# AD8302.net
KiCad netlist of a schematic drawn in EasyEDA Pro
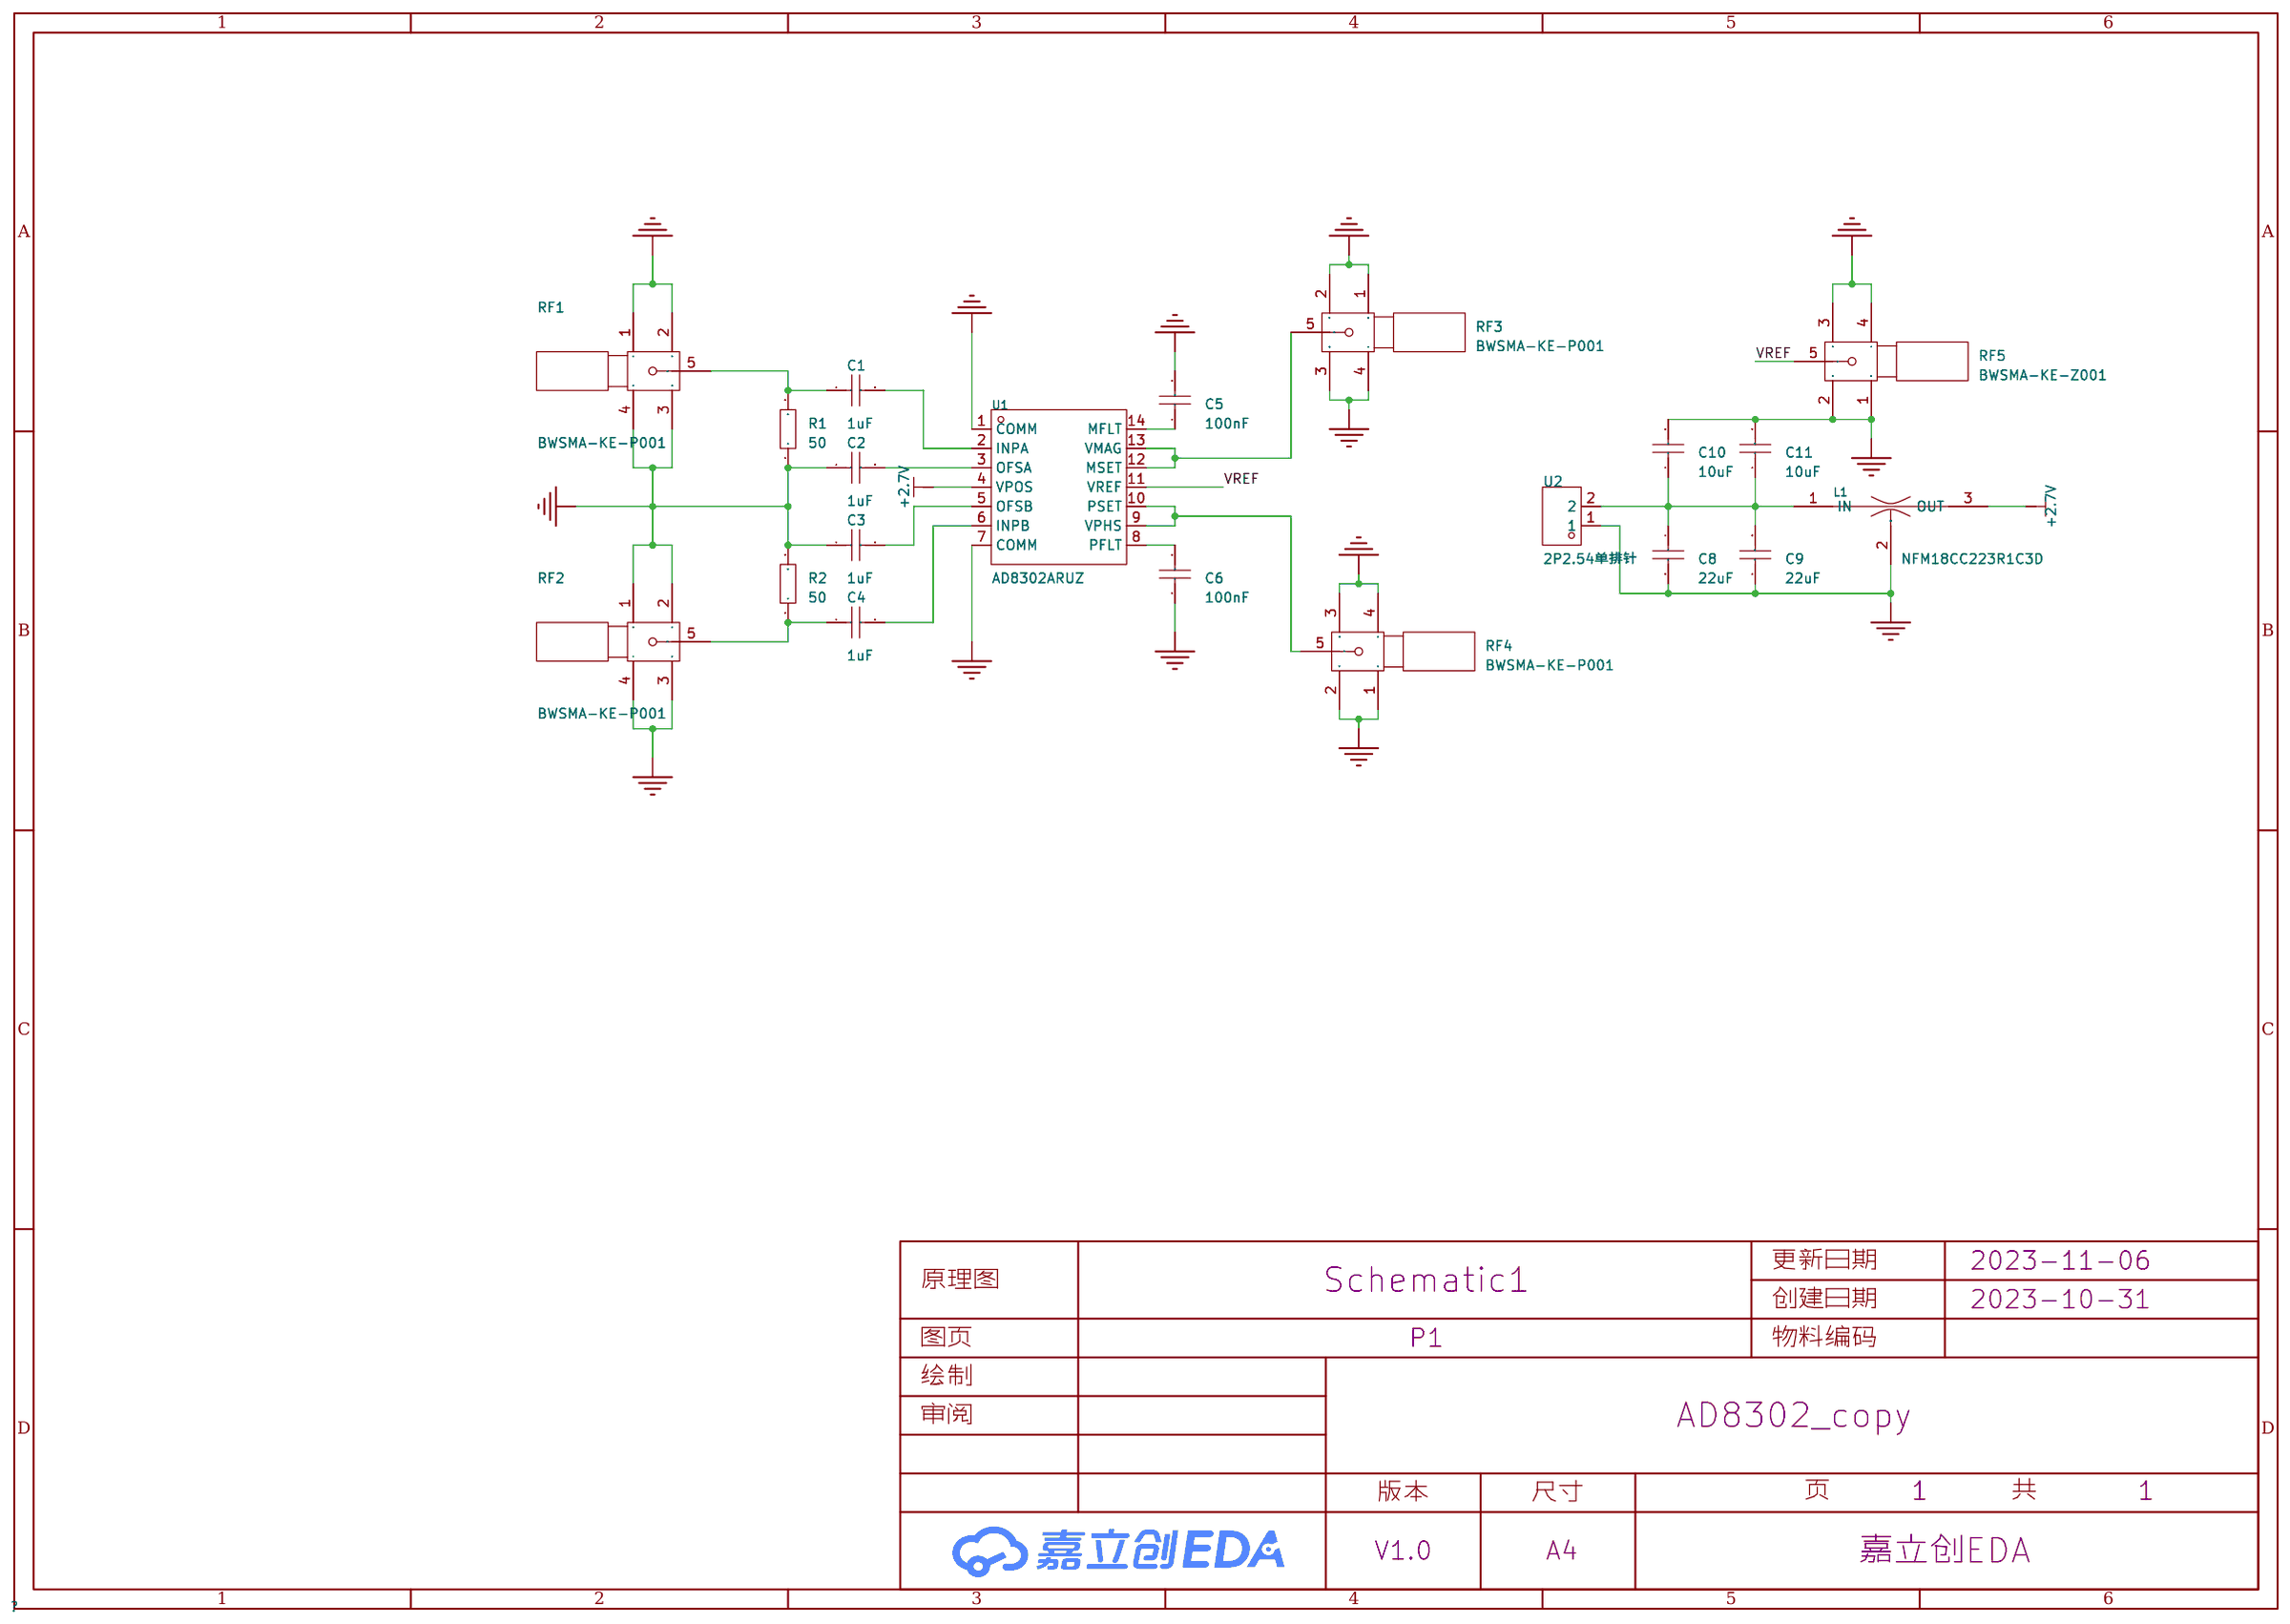
[diagram p0: schematic sheet]

(export (version "E")
  (design (tool "Eeschema 10.0.6"))
  (components
    (comp (ref "C1")
      (value "1uF")
      (footprint "easyedapro:C0603")
      (description "容值:1uF;精度:±10%;额定电压:50V;材质(温度系数):X5R;")
      (fields
        (field (name "Manufacturer Part") "CL10A105KB8NNNC")
        (field (name "Manufacturer") "SAMSUNG(三星)")
      )
      (libsource (lib "easyedapro") (part "CL10A105KB8NNNC"))
    )
    (comp (ref "C2")
      (value "1uF")
      (footprint "easyedapro:C0603")
      (description "容值:1uF;精度:±10%;额定电压:50V;材质(温度系数):X5R;")
      (fields
        (field (name "Manufacturer Part") "CL10A105KB8NNNC")
        (field (name "Manufacturer") "SAMSUNG(三星)")
      )
      (libsource (lib "easyedapro") (part "CL10A105KB8NNNC"))
    )
    (comp (ref "C3")
      (value "1uF")
      (footprint "easyedapro:C0603")
      (description "容值:1uF;精度:±10%;额定电压:50V;材质(温度系数):X5R;")
      (fields
        (field (name "Manufacturer Part") "CL10A105KB8NNNC")
        (field (name "Manufacturer") "SAMSUNG(三星)")
      )
      (libsource (lib "easyedapro") (part "CL10A105KB8NNNC"))
    )
    (comp (ref "C4")
      (value "1uF")
      (footprint "easyedapro:C0603")
      (description "容值:1uF;精度:±10%;额定电压:50V;材质(温度系数):X5R;")
      (fields
        (field (name "Manufacturer Part") "CL10A105KB8NNNC")
        (field (name "Manufacturer") "SAMSUNG(三星)")
      )
      (libsource (lib "easyedapro") (part "CL10A105KB8NNNC"))
    )
    (comp (ref "C5")
      (value "100nF")
      (footprint "easyedapro:C0603")
      (description "容值:1uF;精度:±10%;额定电压:50V;材质(温度系数):X5R;")
      (fields
        (field (name "Manufacturer Part") "CL10A105KB8NNNC")
        (field (name "Manufacturer") "SAMSUNG(三星)")
      )
      (libsource (lib "easyedapro") (part "CL10A105KB8NNNC"))
    )
    (comp (ref "C6")
      (value "100nF")
      (footprint "easyedapro:C0603")
      (description "容值:1uF;精度:±10%;额定电压:50V;材质(温度系数):X5R;")
      (fields
        (field (name "Manufacturer Part") "CL10A105KB8NNNC")
        (field (name "Manufacturer") "SAMSUNG(三星)")
      )
      (libsource (lib "easyedapro") (part "CL10A105KB8NNNC"))
    )
    (comp (ref "C8")
      (value "22uF")
      (footprint "easyedapro:C0603")
      (description "容值:1uF;精度:±10%;额定电压:50V;材质(温度系数):X5R;")
      (fields
        (field (name "Manufacturer Part") "CL10A105KB8NNNC")
        (field (name "Manufacturer") "SAMSUNG(三星)")
      )
      (libsource (lib "easyedapro") (part "CL10A105KB8NNNC"))
    )
    (comp (ref "C9")
      (value "22uF")
      (footprint "easyedapro:C0603")
      (description "容值:1uF;精度:±10%;额定电压:50V;材质(温度系数):X5R;")
      (fields
        (field (name "Manufacturer Part") "CL10A105KB8NNNC")
        (field (name "Manufacturer") "SAMSUNG(三星)")
      )
      (libsource (lib "easyedapro") (part "CL10A105KB8NNNC"))
    )
    (comp (ref "C10")
      (value "10uF")
      (footprint "easyedapro:C0603")
      (description "容值:1uF;精度:±10%;额定电压:50V;材质(温度系数):X5R;")
      (fields
        (field (name "Manufacturer Part") "CL10A105KB8NNNC")
        (field (name "Manufacturer") "SAMSUNG(三星)")
      )
      (libsource (lib "easyedapro") (part "CL10A105KB8NNNC"))
    )
    (comp (ref "C11")
      (value "10uF")
      (footprint "easyedapro:C0603")
      (description "容值:1uF;精度:±10%;额定电压:50V;材质(温度系数):X5R;")
      (fields
        (field (name "Manufacturer Part") "CL10A105KB8NNNC")
        (field (name "Manufacturer") "SAMSUNG(三星)")
      )
      (libsource (lib "easyedapro") (part "CL10A105KB8NNNC"))
    )
    (comp (ref "L1")
      (value "NFM18CC223R1C3D")
      (footprint "easyedapro:FILTER-SMD_3P-L1.6-W0.8-L_NFM18CC223R1C3D")
      (description "电容量:22nF;精度:±20%;直流电阻:50mΩ;")
      (fields (field (name "Manufacturer") "muRata(村田)"))
      (libsource (lib "easyedapro") (part "NFM18CC223R1C3D"))
    )
    (comp (ref "R1") (value "50") (footprint "easyedapro:R0603") (libsource (lib "easyedapro") (part "电阻")))
    (comp (ref "R2") (value "50") (footprint "easyedapro:R0603") (libsource (lib "easyedapro") (part "电阻")))
    (comp (ref "RF1")
      (value "BWSMA-KE-P001")
      (footprint "easyedapro:SMA-SMD_BWSMA-KE-P001")
      (description "连接器类型:板端;射频系列:SMA;接口类型:内孔;端口数量:1;阻抗:50Ω;频率-最大值:12.4GHz;样式:偏脚;接口直径:5.2mm;接口长度/高度:-;工作温度范围:-;")
      (fields (field (name "Manufacturer") "BAT WIRELESS(蝙蝠无线)"))
      (libsource (lib "easyedapro") (part "BWSMA-KE-P001"))
    )
    (comp (ref "RF2")
      (value "BWSMA-KE-P001")
      (footprint "easyedapro:SMA-SMD_BWSMA-KE-P001")
      (description "连接器类型:板端;射频系列:SMA;接口类型:内孔;端口数量:1;阻抗:50Ω;频率-最大值:12.4GHz;样式:偏脚;接口直径:5.2mm;接口长度/高度:-;工作温度范围:-;")
      (fields (field (name "Manufacturer") "BAT WIRELESS(蝙蝠无线)"))
      (libsource (lib "easyedapro") (part "BWSMA-KE-P001"))
    )
    (comp (ref "RF3")
      (value "BWSMA-KE-P001")
      (footprint "easyedapro:SMA-SMD_BWSMA-KE-P001")
      (description "连接器类型:板端;射频系列:SMA;接口类型:内孔;端口数量:1;阻抗:50Ω;频率-最大值:12.4GHz;样式:偏脚;接口直径:5.2mm;接口长度/高度:-;工作温度范围:-;")
      (fields (field (name "Manufacturer") "BAT WIRELESS(蝙蝠无线)"))
      (libsource (lib "easyedapro") (part "BWSMA-KE-P001"))
    )
    (comp (ref "RF4")
      (value "BWSMA-KE-P001")
      (footprint "easyedapro:SMA-SMD_BWSMA-KE-P001")
      (description "连接器类型:板端;射频系列:SMA;接口类型:内孔;端口数量:1;阻抗:50Ω;频率-最大值:12.4GHz;样式:偏脚;接口直径:5.2mm;接口长度/高度:-;工作温度范围:-;")
      (fields (field (name "Manufacturer") "BAT WIRELESS(蝙蝠无线)"))
      (libsource (lib "easyedapro") (part "BWSMA-KE-P001"))
    )
    (comp (ref "RF5")
      (value "BWSMA-KE-Z001")
      (footprint "easyedapro:SMA-TH_BWSMA-KE-Z001")
      (description "连接器类型:板端;射频系列:SMA;接口类型:内孔;端口数量:1;阻抗:50Ω;频率-最大值:12.4GHz;样式:正脚;接口直径:-;接口长度/高度:-;工作温度范围:-65°C~+165°C;")
      (fields (field (name "Manufacturer") "BAT WIRELESS(蝙蝠无线)"))
      (libsource (lib "easyedapro") (part "BWSMA-KE-Z001"))
    )
    (comp (ref "U1")
      (value "AD8302ARUZ")
      (footprint "easyedapro:TSSOP-14_L5.0-W4.4-P0.65-LS6.4-BL")
      (description "应用领域:通用;频率范围:2.7GHz;输入范围:-60dBm~0dBm;精度:±0.5dB;")
      (fields (field (name "Manufacturer") "ADI(亚德诺)"))
      (libsource (lib "easyedapro") (part "AD8302ARUZ"))
    )
    (comp (ref "U2")
      (value "2P2.54单排针")
      (footprint "easyedapro:HDR-TH_2P-P2.54-V-M")
      (libsource (lib "easyedapro") (part "2P2.54单排针"))
    )
  )
  (nets
    (net (code "1") (name "+2.7V") (class "Default")
      (node (ref "L1") (pin "3") (pinfunction "OUT_3") (pintype "input"))
      (node (ref "U1") (pin "4") (pinfunction "VPOS_4") (pintype "input"))
    )
    (net (code "2") (name "/VREF") (class "Default")
      (node (ref "RF5") (pin "5") (pinfunction "5_5") (pintype "input"))
      (node (ref "U1") (pin "11") (pinfunction "VREF_11") (pintype "input"))
    )
    (net (code "3") (name "GND") (class "Default")
      (node (ref "C10") (pin "2") (pinfunction "2_2") (pintype "input"))
      (node (ref "C11") (pin "2") (pinfunction "2_2") (pintype "input"))
      (node (ref "C2") (pin "1") (pinfunction "1_1") (pintype "input"))
      (node (ref "C3") (pin "1") (pinfunction "1_1") (pintype "input"))
      (node (ref "C5") (pin "2") (pinfunction "2_2") (pintype "input"))
      (node (ref "C6") (pin "2") (pinfunction "2_2") (pintype "input"))
      (node (ref "C8") (pin "2") (pinfunction "2_2") (pintype "input"))
      (node (ref "C9") (pin "1") (pinfunction "1_1") (pintype "input"))
      (node (ref "L1") (pin "2") (pinfunction "GND_2") (pintype "input"))
      (node (ref "R1") (pin "1") (pinfunction "1_1") (pintype "input"))
      (node (ref "R2") (pin "2") (pinfunction "2_2") (pintype "input"))
      (node (ref "RF1") (pin "1") (pinfunction "1_1") (pintype "input"))
      (node (ref "RF1") (pin "2") (pinfunction "2_2") (pintype "input"))
      (node (ref "RF1") (pin "3") (pinfunction "3_3") (pintype "input"))
      (node (ref "RF1") (pin "4") (pinfunction "4_4") (pintype "input"))
      (node (ref "RF2") (pin "1") (pinfunction "1_1") (pintype "input"))
      (node (ref "RF2") (pin "2") (pinfunction "2_2") (pintype "input"))
      (node (ref "RF2") (pin "3") (pinfunction "3_3") (pintype "input"))
      (node (ref "RF2") (pin "4") (pinfunction "4_4") (pintype "input"))
      (node (ref "RF3") (pin "1") (pinfunction "1_1") (pintype "input"))
      (node (ref "RF3") (pin "2") (pinfunction "2_2") (pintype "input"))
      (node (ref "RF3") (pin "3") (pinfunction "3_3") (pintype "input"))
      (node (ref "RF3") (pin "4") (pinfunction "4_4") (pintype "input"))
      (node (ref "RF4") (pin "1") (pinfunction "1_1") (pintype "input"))
      (node (ref "RF4") (pin "2") (pinfunction "2_2") (pintype "input"))
      (node (ref "RF4") (pin "3") (pinfunction "3_3") (pintype "input"))
      (node (ref "RF4") (pin "4") (pinfunction "4_4") (pintype "input"))
      (node (ref "RF5") (pin "1") (pinfunction "1_1") (pintype "input"))
      (node (ref "RF5") (pin "2") (pinfunction "2_2") (pintype "input"))
      (node (ref "RF5") (pin "3") (pinfunction "3_3") (pintype "input"))
      (node (ref "RF5") (pin "4") (pinfunction "4_4") (pintype "input"))
      (node (ref "U1") (pin "1") (pinfunction "COMM_1") (pintype "input"))
      (node (ref "U1") (pin "7") (pinfunction "COMM_7") (pintype "input"))
      (node (ref "U2") (pin "1") (pinfunction "1_1") (pintype "input"))
    )
    (net (code "4") (name "Net-(C1-Pad1)") (class "Default")
      (node (ref "C1") (pin "1") (pinfunction "1_1") (pintype "input"))
      (node (ref "R1") (pin "2") (pinfunction "2_2") (pintype "input"))
      (node (ref "RF1") (pin "5") (pinfunction "5_5") (pintype "input"))
    )
    (net (code "5") (name "Net-(C4-Pad1)") (class "Default")
      (node (ref "C4") (pin "1") (pinfunction "1_1") (pintype "input"))
      (node (ref "R2") (pin "1") (pinfunction "1_1") (pintype "input"))
      (node (ref "RF2") (pin "5") (pinfunction "5_5") (pintype "input"))
    )
    (net (code "6") (name "Net-(L1-IN)") (class "Default")
      (node (ref "C10") (pin "1") (pinfunction "1_1") (pintype "input"))
      (node (ref "C11") (pin "1") (pinfunction "1_1") (pintype "input"))
      (node (ref "C8") (pin "1") (pinfunction "1_1") (pintype "input"))
      (node (ref "C9") (pin "2") (pinfunction "2_2") (pintype "input"))
      (node (ref "L1") (pin "1") (pinfunction "IN_1") (pintype "input"))
      (node (ref "U2") (pin "2") (pinfunction "2_2") (pintype "input"))
    )
    (net (code "7") (name "Net-(U1-INPA)") (class "Default")
      (node (ref "C1") (pin "2") (pinfunction "2_2") (pintype "input"))
      (node (ref "U1") (pin "2") (pinfunction "INPA_2") (pintype "input"))
    )
    (net (code "8") (name "Net-(U1-INPB)") (class "Default")
      (node (ref "C4") (pin "2") (pinfunction "2_2") (pintype "input"))
      (node (ref "U1") (pin "6") (pinfunction "INPB_6") (pintype "input"))
    )
    (net (code "9") (name "Net-(U1-MFLT)") (class "Default")
      (node (ref "C5") (pin "1") (pinfunction "1_1") (pintype "input"))
      (node (ref "U1") (pin "14") (pinfunction "MFLT_14") (pintype "input"))
    )
    (net (code "10") (name "Net-(U1-MSET)") (class "Default")
      (node (ref "RF3") (pin "5") (pinfunction "5_5") (pintype "input"))
      (node (ref "U1") (pin "12") (pinfunction "MSET_12") (pintype "input"))
      (node (ref "U1") (pin "13") (pinfunction "VMAG_13") (pintype "input"))
    )
    (net (code "11") (name "Net-(U1-OFSA)") (class "Default")
      (node (ref "C2") (pin "2") (pinfunction "2_2") (pintype "input"))
      (node (ref "U1") (pin "3") (pinfunction "OFSA_3") (pintype "input"))
    )
    (net (code "12") (name "Net-(U1-OFSB)") (class "Default")
      (node (ref "C3") (pin "2") (pinfunction "2_2") (pintype "input"))
      (node (ref "U1") (pin "5") (pinfunction "OFSB_5") (pintype "input"))
    )
    (net (code "13") (name "Net-(U1-PFLT)") (class "Default")
      (node (ref "C6") (pin "1") (pinfunction "1_1") (pintype "input"))
      (node (ref "U1") (pin "8") (pinfunction "PFLT_8") (pintype "input"))
    )
    (net (code "14") (name "Net-(U1-PSET)") (class "Default")
      (node (ref "RF4") (pin "5") (pinfunction "5_5") (pintype "input"))
      (node (ref "U1") (pin "10") (pinfunction "PSET_10") (pintype "input"))
      (node (ref "U1") (pin "9") (pinfunction "VPHS_9") (pintype "input"))
    )
  )
)
